# module_4_TEMP_HUMIDITY.net
KiCad netlist of a schematic drawn in Altium Designer
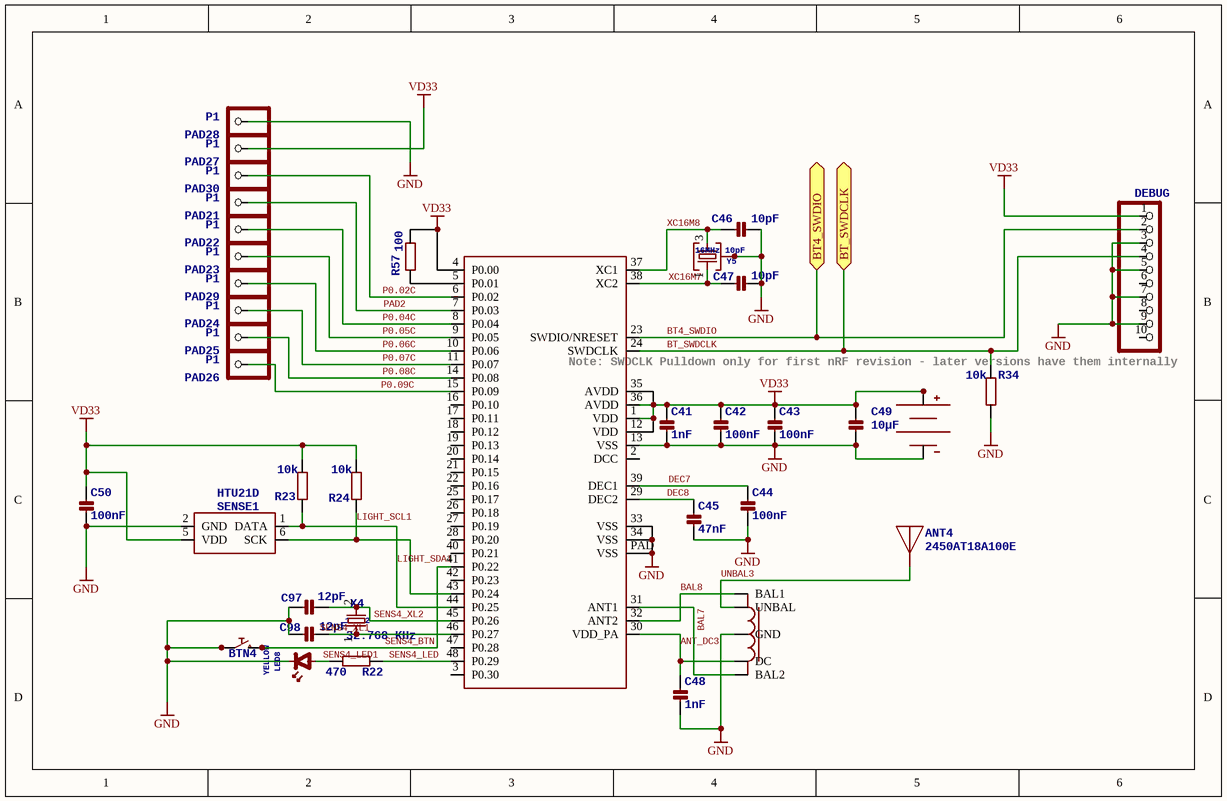
[diagram p0: module 4_TEMP_HUMIDITY.SchDoc]

(export (version "E")
  (design (tool "Eeschema 10.0.6"))
  (components
    (comp (ref "ANT4")
      (value "2450AT18A100E")
      (footprint "1206_MINIMELF_COMBO")
      (description "2.45 GHz Antenna")
      (libsource (lib "WunderBar_v101") (part "ANTENNA_MONOPOLE1206"))
    )
    (comp (ref "BALUN4")
      (value "2450BM14A0002T")
      (footprint "6-PIN-0603")
      (description "2.45 GHz Impedance Matched Balun-Filter")
      (libsource (lib "WunderBar_v101") (part "BALUN"))
    )
    (comp (ref "BAT4")
      (value "BATTERYBK-912")
      (footprint "BK-912")
      (description "Coin battery holder")
      (libsource (lib "WunderBar_v101") (part "BATTERYBK-912"))
    )
    (comp (ref "BT4")
      (value "NRF51822QFN48")
      (footprint "QFN48_EP")
      (description "Nordic Bluetooth 4.0 low energy modul")
      (libsource (lib "WunderBar_v101") (part "NRF51822QFN48"))
    )
    (comp (ref "BTN4")
      (value "Tact Sw 4.6x2.8")
      (footprint "CK-KMR2")
      (description "Push button")
      (libsource (lib "WunderBar_v101") (part "PUSHBUTTONKMR2XX"))
    )
    (comp (ref "C41")
      (value "1nF")
      (footprint "0402")
      (description "Ceramic Capacitor")
      (libsource (lib "WunderBar_v101") (part "CAP_CERAMIC0402"))
    )
    (comp (ref "C42")
      (value "100nF")
      (footprint "0402")
      (description "Ceramic Capacitor")
      (libsource (lib "WunderBar_v101") (part "CAP_CERAMIC0402"))
    )
    (comp (ref "C43")
      (value "100nF")
      (footprint "0402")
      (description "Ceramic Capacitor")
      (libsource (lib "WunderBar_v101") (part "CAP_CERAMIC0402"))
    )
    (comp (ref "C44")
      (value "100nF")
      (footprint "0402")
      (description "Ceramic Capacitor")
      (libsource (lib "WunderBar_v101") (part "CAP_CERAMIC0402"))
    )
    (comp (ref "C45")
      (value "47nF")
      (footprint "0402")
      (description "Ceramic Capacitor")
      (libsource (lib "WunderBar_v101") (part "CAP_CERAMIC0402"))
    )
    (comp (ref "C46")
      (value "10pF")
      (footprint "0402")
      (description "Ceramic Capacitor")
      (libsource (lib "") (part "CAP_CERAMIC0402_1"))
    )
    (comp (ref "C47")
      (value "10pF")
      (footprint "0402")
      (description "Ceramic Capacitor")
      (libsource (lib "") (part "CAP_CERAMIC0402_1"))
    )
    (comp (ref "C48")
      (value "1nF")
      (footprint "0402")
      (description "Ceramic Capacitor")
      (libsource (lib "WunderBar_v101") (part "CAP_CERAMIC0402"))
    )
    (comp (ref "C49")
      (value "10µF")
      (footprint "0603")
      (description "Ceramic Capacitor")
      (libsource (lib "WunderBar_v101") (part "CAP_CERAMIC0603"))
    )
    (comp (ref "C50")
      (value "100nF")
      (footprint "0402")
      (description "Ceramic Capacitor")
      (libsource (lib "WunderBar_v101") (part "CAP_CERAMIC0402"))
    )
    (comp (ref "C97")
      (value "12pF")
      (footprint "0402")
      (description "Ceramic Capacitor")
      (libsource (lib "") (part "CAP_CERAMIC0402_1"))
    )
    (comp (ref "C98")
      (value "12pF")
      (footprint "0402")
      (description "Ceramic Capacitor")
      (libsource (lib "") (part "CAP_CERAMIC0402_1"))
    )
    (comp (ref "DEBUG4")
      (value "DEBUG")
      (footprint "2X05_SMT")
      (description "cortex DEBUG connector")
      (libsource (lib "WunderBar_v101") (part "HEADER-2X5SMD-1.27MM"))
    )
    (comp (ref "LED8")
      (value "YELLOW")
      (footprint "0402_POLAR")
      (description "LED common")
      (libsource (lib "WunderBar_v101") (part "LED0402"))
    )
    (comp (ref "PAD21")
      (value "P1")
      (footprint "PCB_MEDIUM_RECT_PAD")
      (description "<b>PIN HEADER</b>")
      (libsource (lib "WunderBar_v101") (part "HEADER-1X1SMD_MEDIUM"))
    )
    (comp (ref "PAD22")
      (value "P1")
      (footprint "PCB_MEDIUM_RECT_PAD")
      (description "<b>PIN HEADER</b>")
      (libsource (lib "WunderBar_v101") (part "HEADER-1X1SMD_MEDIUM"))
    )
    (comp (ref "PAD23")
      (value "P1")
      (footprint "PCB_MEDIUM_RECT_PAD")
      (description "<b>PIN HEADER</b>")
      (libsource (lib "WunderBar_v101") (part "HEADER-1X1SMD_MEDIUM"))
    )
    (comp (ref "PAD24")
      (value "P1")
      (footprint "PCB_MEDIUM_RECT_PAD")
      (description "<b>PIN HEADER</b>")
      (libsource (lib "WunderBar_v101") (part "HEADER-1X1SMD_MEDIUM"))
    )
    (comp (ref "PAD25")
      (value "P1")
      (footprint "PCB_MEDIUM_RECT_PAD")
      (description "<b>PIN HEADER</b>")
      (libsource (lib "WunderBar_v101") (part "HEADER-1X1SMD_MEDIUM"))
    )
    (comp (ref "PAD26")
      (value "P1")
      (footprint "PCB_MEDIUM_RECT_PAD")
      (description "<b>PIN HEADER</b>")
      (libsource (lib "WunderBar_v101") (part "HEADER-1X1SMD_MEDIUM"))
    )
    (comp (ref "PAD27")
      (value "P1")
      (footprint "PCB_MEDIUM_RECT_PAD")
      (description "<b>PIN HEADER</b>")
      (libsource (lib "WunderBar_v101") (part "HEADER-1X1SMD_MEDIUM"))
    )
    (comp (ref "PAD28")
      (value "P1")
      (footprint "PCB_MEDIUM_RECT_PAD")
      (description "<b>PIN HEADER</b>")
      (libsource (lib "WunderBar_v101") (part "HEADER-1X1SMD_MEDIUM"))
    )
    (comp (ref "PAD29")
      (value "P1")
      (footprint "PCB_MEDIUM_RECT_PAD")
      (description "<b>PIN HEADER</b>")
      (libsource (lib "WunderBar_v101") (part "HEADER-1X1SMD_MEDIUM"))
    )
    (comp (ref "PAD30")
      (value "P1")
      (footprint "PCB_MEDIUM_RECT_PAD")
      (description "<b>PIN HEADER</b>")
      (libsource (lib "WunderBar_v101") (part "HEADER-1X1SMD_MEDIUM"))
    )
    (comp (ref "R22")
      (value "470")
      (footprint "0402")
      (description "RESISTOR")
      (libsource (lib "WunderBar_v101") (part "R-EU_0402"))
    )
    (comp (ref "R23")
      (value "10k")
      (footprint "0402")
      (description "RESISTOR")
      (libsource (lib "WunderBar_v101") (part "R-EU_0402"))
    )
    (comp (ref "R24")
      (value "10k")
      (footprint "0402")
      (description "RESISTOR")
      (libsource (lib "WunderBar_v101") (part "R-EU_0402"))
    )
    (comp (ref "R34")
      (value "10k")
      (footprint "0402")
      (description "RESISTOR")
      (libsource (lib "WunderBar_v101") (part "R-EU_0402"))
    )
    (comp (ref "R57")
      (value "100")
      (footprint "0402")
      (description "RESISTOR")
      (libsource (lib "WunderBar_v101") (part "R-EU_0402"))
    )
    (comp (ref "SENSE1")
      (value "HTU21D")
      (footprint "HTU21D")
      (description "Humidity and temperature sensor")
      (libsource (lib "WunderBar_v101") (part "HTU21D"))
    )
    (comp (ref "X4")
      (value "32.768 KHz")
      (footprint "1206_MINIMELF_COMBO")
      (description "CL05C120JB5")
      (fields (field (name "1") "1") (field (name "2") "2"))
      (libsource (lib "WunderBar_v101") (part "CRYSTAL1206"))
    )
    (comp (ref "Y5")
      (value "16MHz 10pF")
      (footprint "CRYSTAL25X20")
      (description "16MHz crystal 2.5x2mm")
      (libsource (lib "WunderBar_v101") (part "CRYSTAL_WITH_GROUND25X20"))
    )
  )
  (nets
    (net (code "1") (name "/ANT_DC3") (class "Default")
      (node (ref "BALUN4") (pin "5") (pinfunction "DC_5") (pintype "power_in"))
      (node (ref "BT4") (pin "30") (pinfunction "VDD_PA_30") (pintype "passive"))
      (node (ref "C48") (pin "1") (pinfunction "1_1") (pintype "passive"))
    )
    (net (code "2") (name "/BAL7") (class "Default")
      (node (ref "BALUN4") (pin "4") (pinfunction "BAL2_4") (pintype "passive"))
      (node (ref "BT4") (pin "31") (pinfunction "ANT1_31") (pintype "passive"))
    )
    (net (code "3") (name "/BAL8") (class "Default")
      (node (ref "BALUN4") (pin "3") (pinfunction "BAL1_3") (pintype "passive"))
      (node (ref "BT4") (pin "32") (pinfunction "ANT2_32") (pintype "passive"))
    )
    (net (code "4") (name "/BT4_SWDIO") (class "Default")
      (node (ref "BT4") (pin "23") (pinfunction "SWDIO/NRESET_23") (pintype "passive"))
      (node (ref "DEBUG4") (pin "2") (pinfunction "2_2") (pintype "passive"))
    )
    (net (code "5") (name "/BT_SWDCLK") (class "Default")
      (node (ref "BT4") (pin "24") (pinfunction "SWDCLK_24") (pintype "passive"))
      (node (ref "DEBUG4") (pin "4") (pinfunction "4_4") (pintype "passive"))
      (node (ref "R34") (pin "2") (pinfunction "2_2") (pintype "passive"))
    )
    (net (code "6") (name "/DEC7") (class "Default")
      (node (ref "BT4") (pin "39") (pinfunction "DEC1_39") (pintype "passive"))
      (node (ref "C44") (pin "1") (pinfunction "1_1") (pintype "passive"))
    )
    (net (code "7") (name "/DEC8") (class "Default")
      (node (ref "BT4") (pin "29") (pinfunction "DEC2_29") (pintype "passive"))
      (node (ref "C45") (pin "1") (pinfunction "1_1") (pintype "passive"))
    )
    (net (code "8") (name "/LIGHT_SCL1") (class "Default")
      (node (ref "BT4") (pin "43") (pinfunction "P0.24_43") (pintype "passive"))
      (node (ref "R24") (pin "1") (pinfunction "1_1") (pintype "passive"))
      (node (ref "SENSE1") (pin "6") (pinfunction "SCK_6") (pintype "passive"))
    )
    (net (code "9") (name "/LIGHT_SDA1") (class "Default")
      (node (ref "BT4") (pin "44") (pinfunction "P0.25_44") (pintype "passive"))
      (node (ref "R23") (pin "1") (pinfunction "1_1") (pintype "passive"))
      (node (ref "SENSE1") (pin "1") (pinfunction "DATA_1") (pintype "passive"))
    )
    (net (code "10") (name "/P0.02C") (class "Default")
      (node (ref "BT4") (pin "6") (pinfunction "P0.02_6") (pintype "passive"))
      (node (ref "PAD30") (pin "1") (pinfunction "1_1") (pintype "passive"))
    )
    (net (code "11") (name "/P0.04C") (class "Default")
      (node (ref "BT4") (pin "8") (pinfunction "P0.04_8") (pintype "passive"))
      (node (ref "PAD22") (pin "1") (pinfunction "1_1") (pintype "passive"))
    )
    (net (code "12") (name "/P0.05C") (class "Default")
      (node (ref "BT4") (pin "9") (pinfunction "P0.05_9") (pintype "passive"))
      (node (ref "PAD23") (pin "1") (pinfunction "1_1") (pintype "passive"))
    )
    (net (code "13") (name "/P0.06C") (class "Default")
      (node (ref "BT4") (pin "10") (pinfunction "P0.06_10") (pintype "passive"))
      (node (ref "PAD29") (pin "1") (pinfunction "1_1") (pintype "passive"))
    )
    (net (code "14") (name "/P0.07C") (class "Default")
      (node (ref "BT4") (pin "11") (pinfunction "P0.07_11") (pintype "passive"))
      (node (ref "PAD24") (pin "1") (pinfunction "1_1") (pintype "passive"))
    )
    (net (code "15") (name "/P0.08C") (class "Default")
      (node (ref "BT4") (pin "14") (pinfunction "P0.08_14") (pintype "passive"))
      (node (ref "PAD25") (pin "1") (pinfunction "1_1") (pintype "passive"))
    )
    (net (code "16") (name "/P0.09C") (class "Default")
      (node (ref "BT4") (pin "15") (pinfunction "P0.09_15") (pintype "passive"))
      (node (ref "PAD26") (pin "1") (pinfunction "1_1") (pintype "passive"))
    )
    (net (code "17") (name "/PAD2") (class "Default")
      (node (ref "BT4") (pin "7") (pinfunction "P0.03_7") (pintype "passive"))
      (node (ref "PAD21") (pin "1") (pinfunction "1_1") (pintype "passive"))
    )
    (net (code "18") (name "/SENS4_BTN") (class "Default")
      (node (ref "BT4") (pin "41") (pinfunction "P0.22_41") (pintype "passive"))
      (node (ref "BTN4") (pin "P3") (pinfunction "3_P3") (pintype "passive"))
      (node (ref "BTN4") (pin "P4") (pinfunction "4_P4") (pintype "passive"))
    )
    (net (code "19") (name "/SENS4_LED") (class "Default")
      (node (ref "BT4") (pin "48") (pinfunction "P0.29_48") (pintype "passive"))
      (node (ref "R22") (pin "1") (pinfunction "1_1") (pintype "passive"))
    )
    (net (code "20") (name "/SENS4_LED1") (class "Default")
      (node (ref "LED8") (pin "A") (pinfunction "ANODE_A") (pintype "passive"))
      (node (ref "R22") (pin "2") (pinfunction "2_2") (pintype "passive"))
    )
    (net (code "22") (name "/SENS4_XL2") (class "Default")
      (node (ref "BT4") (pin "45") (pinfunction "P0.26_45") (pintype "passive"))
      (node (ref "C97") (pin "2") (pinfunction "2_2") (pintype "passive"))
      (node (ref "X4") (pin "2") (pinfunction "2_2") (pintype "passive"))
    )
    (net (code "23") (name "/UNBAL3") (class "Default")
      (node (ref "ANT4") (pin "1") (pinfunction "ANT_1") (pintype "passive"))
      (node (ref "BALUN4") (pin "1") (pinfunction "UNBAL_1") (pintype "passive"))
    )
    (net (code "24") (name "/XC16M7") (class "Default")
      (node (ref "BT4") (pin "38") (pinfunction "XC2_38") (pintype "passive"))
      (node (ref "C47") (pin "1") (pinfunction "1_1") (pintype "passive"))
      (node (ref "Y5") (pin "1") (pinfunction "1_1") (pintype "passive"))
    )
    (net (code "25") (name "/XC16M8") (class "Default")
      (node (ref "BT4") (pin "37") (pinfunction "XC1_37") (pintype "passive"))
      (node (ref "C46") (pin "1") (pinfunction "1_1") (pintype "passive"))
      (node (ref "Y5") (pin "3") (pinfunction "3_3") (pintype "passive"))
    )
    (net (code "26") (name "GND") (class "Default")
      (node (ref "BALUN4") (pin "2") (pinfunction "GND_2") (pintype "power_in"))
      (node (ref "BAT4") (pin "-") (pinfunction "-_-") (pintype "power_in"))
      (node (ref "BT4") (pin "13") (pinfunction "VSS_13") (pintype "passive"))
      (node (ref "BT4") (pin "33") (pinfunction "VSS_33") (pintype "passive"))
      (node (ref "BT4") (pin "34") (pinfunction "VSS_34") (pintype "passive"))
      (node (ref "BT4") (pin "PAD") (pinfunction "VSS_PAD") (pintype "passive"))
      (node (ref "BTN4") (pin "P1") (pinfunction "1_P1") (pintype "passive"))
      (node (ref "BTN4") (pin "P2") (pinfunction "2_P2") (pintype "passive"))
      (node (ref "C41") (pin "2") (pinfunction "2_2") (pintype "passive"))
      (node (ref "C42") (pin "2") (pinfunction "2_2") (pintype "passive"))
      (node (ref "C43") (pin "2") (pinfunction "2_2") (pintype "passive"))
      (node (ref "C44") (pin "2") (pinfunction "2_2") (pintype "passive"))
      (node (ref "C45") (pin "2") (pinfunction "2_2") (pintype "passive"))
      (node (ref "C46") (pin "2") (pinfunction "2_2") (pintype "passive"))
      (node (ref "C47") (pin "2") (pinfunction "2_2") (pintype "passive"))
      (node (ref "C48") (pin "2") (pinfunction "2_2") (pintype "passive"))
      (node (ref "C49") (pin "2") (pinfunction "P2_2") (pintype "passive"))
      (node (ref "C50") (pin "2") (pinfunction "2_2") (pintype "passive"))
      (node (ref "C97") (pin "1") (pinfunction "1_1") (pintype "passive"))
      (node (ref "C98") (pin "1") (pinfunction "1_1") (pintype "passive"))
      (node (ref "DEBUG4") (pin "3") (pinfunction "3_3") (pintype "passive"))
      (node (ref "DEBUG4") (pin "5") (pinfunction "5_5") (pintype "passive"))
      (node (ref "DEBUG4") (pin "7") (pinfunction "7_7") (pintype "passive"))
      (node (ref "DEBUG4") (pin "9") (pinfunction "9_9") (pintype "passive"))
      (node (ref "LED8") (pin "K") (pinfunction "CATHODE_K") (pintype "passive"))
      (node (ref "PAD28") (pin "1") (pinfunction "1_1") (pintype "passive"))
      (node (ref "R34") (pin "1") (pinfunction "1_1") (pintype "passive"))
      (node (ref "SENSE1") (pin "2") (pinfunction "GND_2") (pintype "power_in"))
      (node (ref "Y5") (pin "2") (pinfunction "2_2") (pintype "power_in"))
      (node (ref "Y5") (pin "4") (pinfunction "4_4") (pintype "power_in"))
    )
    (net (code "27") (name "Net-(BT4-P0.01)") (class "Default")
      (node (ref "BT4") (pin "5") (pinfunction "P0.01_5") (pintype "passive"))
      (node (ref "R57") (pin "2") (pinfunction "2_2") (pintype "passive"))
    )
    (net (code "28") (name "Net-(BT4-P0.27)") (class "Default")
      (node (ref "BT4") (pin "46") (pinfunction "P0.27_46") (pintype "passive"))
      (node (ref "C98") (pin "2") (pinfunction "2_2") (pintype "passive"))
      (node (ref "X4") (pin "1") (pinfunction "1_1") (pintype "passive"))
    )
    (net (code "29") (name "VD33") (class "Default")
      (node (ref "BAT4") (pin "+1") (pinfunction "+_+1") (pintype "power_in"))
      (node (ref "BAT4") (pin "+2") (pinfunction "+_+2") (pintype "power_in"))
      (node (ref "BT4") (pin "1") (pinfunction "VDD_1") (pintype "passive"))
      (node (ref "BT4") (pin "12") (pinfunction "VDD_12") (pintype "passive"))
      (node (ref "BT4") (pin "35") (pinfunction "AVDD_35") (pintype "passive"))
      (node (ref "BT4") (pin "36") (pinfunction "AVDD_36") (pintype "passive"))
      (node (ref "BT4") (pin "4") (pinfunction "P0.00_4") (pintype "passive"))
      (node (ref "C41") (pin "1") (pinfunction "1_1") (pintype "passive"))
      (node (ref "C42") (pin "1") (pinfunction "1_1") (pintype "passive"))
      (node (ref "C43") (pin "1") (pinfunction "1_1") (pintype "passive"))
      (node (ref "C49") (pin "1") (pinfunction "P1_1") (pintype "passive"))
      (node (ref "C50") (pin "1") (pinfunction "1_1") (pintype "passive"))
      (node (ref "DEBUG4") (pin "1") (pinfunction "1_1") (pintype "passive"))
      (node (ref "PAD27") (pin "1") (pinfunction "1_1") (pintype "passive"))
      (node (ref "R23") (pin "2") (pinfunction "2_2") (pintype "passive"))
      (node (ref "R24") (pin "2") (pinfunction "2_2") (pintype "passive"))
      (node (ref "R57") (pin "1") (pinfunction "1_1") (pintype "passive"))
      (node (ref "SENSE1") (pin "5") (pinfunction "VDD_5") (pintype "power_in"))
    )
    (net (code "30") (name "unconnected-(BT4-DCC-Pad2)") (class "Default")
      (node (ref "BT4") (pin "2") (pinfunction "DCC_2") (pintype "passive"))
    )
    (net (code "31") (name "unconnected-(BT4-P0.10-Pad16)") (class "Default")
      (node (ref "BT4") (pin "16") (pinfunction "P0.10_16") (pintype "passive"))
    )
    (net (code "32") (name "unconnected-(BT4-P0.11-Pad17)") (class "Default")
      (node (ref "BT4") (pin "17") (pinfunction "P0.11_17") (pintype "passive"))
    )
    (net (code "33") (name "unconnected-(BT4-P0.12-Pad18)") (class "Default")
      (node (ref "BT4") (pin "18") (pinfunction "P0.12_18") (pintype "passive"))
    )
    (net (code "34") (name "unconnected-(BT4-P0.13-Pad19)") (class "Default")
      (node (ref "BT4") (pin "19") (pinfunction "P0.13_19") (pintype "passive"))
    )
    (net (code "35") (name "unconnected-(BT4-P0.14-Pad20)") (class "Default")
      (node (ref "BT4") (pin "20") (pinfunction "P0.14_20") (pintype "passive"))
    )
    (net (code "36") (name "unconnected-(BT4-P0.15-Pad21)") (class "Default")
      (node (ref "BT4") (pin "21") (pinfunction "P0.15_21") (pintype "passive"))
    )
    (net (code "37") (name "unconnected-(BT4-P0.16-Pad22)") (class "Default")
      (node (ref "BT4") (pin "22") (pinfunction "P0.16_22") (pintype "passive"))
    )
    (net (code "38") (name "unconnected-(BT4-P0.17-Pad25)") (class "Default")
      (node (ref "BT4") (pin "25") (pinfunction "P0.17_25") (pintype "passive"))
    )
    (net (code "39") (name "unconnected-(BT4-P0.18-Pad26)") (class "Default")
      (node (ref "BT4") (pin "26") (pinfunction "P0.18_26") (pintype "passive"))
    )
    (net (code "40") (name "unconnected-(BT4-P0.19-Pad27)") (class "Default")
      (node (ref "BT4") (pin "27") (pinfunction "P0.19_27") (pintype "passive"))
    )
    (net (code "41") (name "unconnected-(BT4-P0.20-Pad28)") (class "Default")
      (node (ref "BT4") (pin "28") (pinfunction "P0.20_28") (pintype "passive"))
    )
    (net (code "42") (name "unconnected-(BT4-P0.21-Pad40)") (class "Default")
      (node (ref "BT4") (pin "40") (pinfunction "P0.21_40") (pintype "passive"))
    )
    (net (code "43") (name "unconnected-(BT4-P0.23-Pad42)") (class "Default")
      (node (ref "BT4") (pin "42") (pinfunction "P0.23_42") (pintype "passive"))
    )
    (net (code "44") (name "unconnected-(BT4-P0.28-Pad47)") (class "Default")
      (node (ref "BT4") (pin "47") (pinfunction "P0.28_47") (pintype "passive"))
    )
    (net (code "45") (name "unconnected-(BT4-P0.30-Pad3)") (class "Default")
      (node (ref "BT4") (pin "3") (pinfunction "P0.30_3") (pintype "passive"))
    )
    (net (code "46") (name "unconnected-(DEBUG4-Pad6)") (class "Default")
      (node (ref "DEBUG4") (pin "6") (pinfunction "6_6") (pintype "passive"))
    )
    (net (code "47") (name "unconnected-(DEBUG4-Pad8)") (class "Default")
      (node (ref "DEBUG4") (pin "8") (pinfunction "8_8") (pintype "passive"))
    )
    (net (code "48") (name "unconnected-(DEBUG4-Pad10)") (class "Default")
      (node (ref "DEBUG4") (pin "10") (pinfunction "10_10") (pintype "passive"))
    )
  )
)
